# DAUGHTERBOARD.net
KiCad netlist of a schematic drawn in Altium Designer
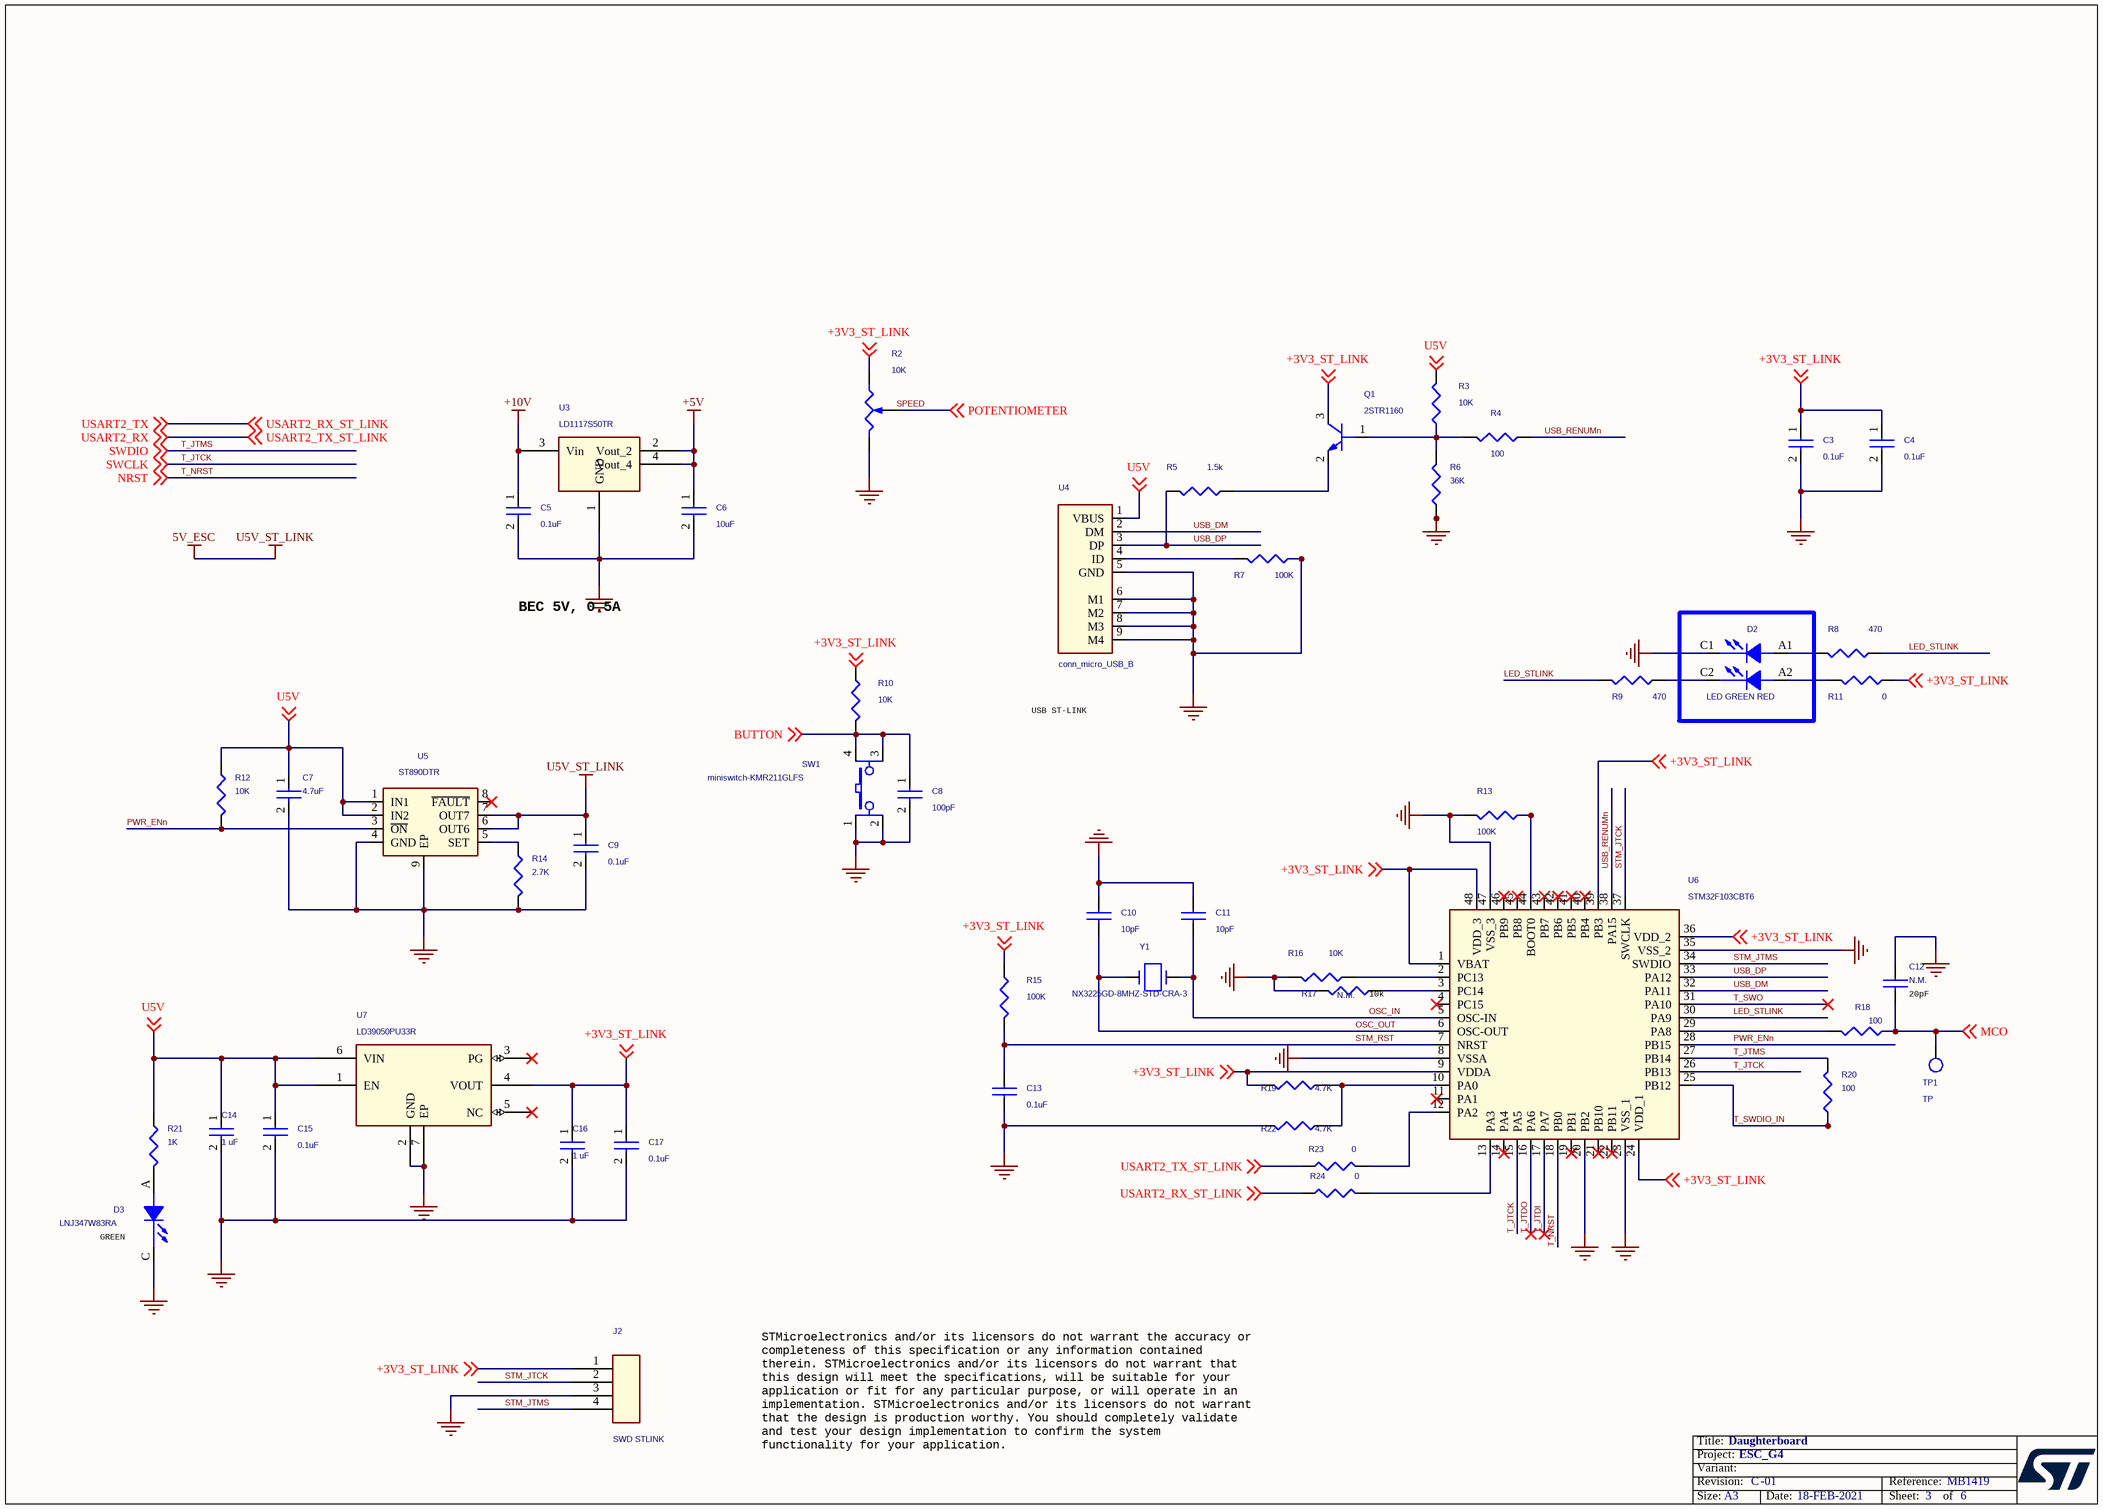
[diagram p0: DAUGHTERBOARD.SchDoc]

(export (version "E")
  (design (tool "Eeschema 10.0.6"))
  (components
    (comp (ref "C3")
      (value "0.1uF")
      (footprint "C_0402")
      (description "CAP CER 0.1UF 16V X7R 0402")
      (fields (field (name "MANUFACTURER") "Wurth Electronics Inc.") (field (name "TOLERANCE") "10%"))
      (libsource (lib "*") (part "CAP_Dup1"))
    )
    (comp (ref "C4")
      (value "0.1uF")
      (footprint "C_0402")
      (description "CAP CER 0.1UF 16V X7R 0402")
      (fields (field (name "MANUFACTURER") "Wurth Electronics Inc.") (field (name "TOLERANCE") "10%"))
      (libsource (lib "*") (part "CAP_Dup1"))
    )
    (comp (ref "C5")
      (value "0.1uF")
      (footprint "C_0402")
      (description "CAP CER 0.1UF 16V X7R 0402")
      (fields (field (name "MANUFACTURER") "Wurth Electronics Inc.") (field (name "TOLERANCE") "10%"))
      (libsource (lib "*") (part "CAP_Dup1"))
    )
    (comp (ref "C6")
      (value "10uF")
      (footprint "C_0805")
      (description "CAP CER 10UF 16V X5R 0805")
      (fields (field (name "MANUFACTURER") "Wurth Electronics Inc.") (field (name "TOLERANCE") "20%"))
      (libsource (lib "*") (part "CAP_Dup1"))
    )
    (comp (ref "C7")
      (value "4.7uF")
      (footprint "C_0805")
      (description "CAP CER 4.7UF 16V X5R 0805")
      (fields (field (name "PART_NUMBER") "TMP-410") (field (name "TOLERANCE") "20%"))
      (libsource (lib "*") (part "CAP_Dup1"))
    )
    (comp (ref "C8")
      (value "100pF")
      (footprint "C_0402")
      (description "CAP CER 100PF 10V C0G/NP0 0402")
      (fields (field (name "PART_NUMBER") "TMP-412") (field (name "TOLERANCE") "5%"))
      (libsource (lib "*") (part "CAP_Dup1"))
    )
    (comp (ref "C9")
      (value "0.1uF")
      (footprint "C_0402")
      (description "CAP CER 0.1UF 16V X7R 0402")
      (fields (field (name "MANUFACTURER") "Wurth Electronics Inc.") (field (name "TOLERANCE") "10%"))
      (libsource (lib "*") (part "CAP_Dup1"))
    )
    (comp (ref "C10")
      (value "10pF")
      (footprint "C_0402")
      (description "CAP CER 10PF 10V C0G/NP0 0402")
      (fields (field (name "PART_NUMBER") "TMP-395") (field (name "TOLERANCE") "5%"))
      (libsource (lib "*") (part "CAP_7"))
    )
    (comp (ref "C11")
      (value "10pF")
      (footprint "C_0402")
      (description "CAP CER 10PF 10V C0G/NP0 0402")
      (fields (field (name "PART_NUMBER") "TMP-395") (field (name "TOLERANCE") "5%"))
      (libsource (lib "*") (part "CAP_7"))
    )
    (comp (ref "C12")
      (value "N.M.")
      (footprint "C_0402")
      (description "CAP CER 0402-NOT MOUNTED")
      (fields (field (name "PART_NUMBER") "TMP-408"))
      (libsource (lib "*") (part "CAP_6"))
    )
    (comp (ref "C13")
      (value "0.1uF")
      (footprint "C_0402")
      (description "CAP CER 0.1UF 16V X7R 0402")
      (fields (field (name "PART_NUMBER") "CAP-00000053") (field (name "TOLERANCE") "10%"))
      (libsource (lib "*") (part "CAP_8"))
    )
    (comp (ref "C14")
      (value "1 uF")
      (footprint "C_0603")
      (description "CAP CER 1UF 16V X5R 0603")
      (fields (field (name "PART_NUMBER") "TMP-302") (field (name "TOLERANCE") "10%"))
      (libsource (lib "*") (part "CAP_Dup1"))
    )
    (comp (ref "C15")
      (value "0.1uF")
      (footprint "C_0603")
      (description "CAP CER 0.1UF 16V X7R 0603")
      (fields (field (name "MANUFACTURER") "Wurth Electronics Inc.") (field (name "TOLERANCE") "10%"))
      (libsource (lib "*") (part "CAP_Dup1"))
    )
    (comp (ref "C16")
      (value "1 uF")
      (footprint "C_0603")
      (description "CAP CER 1UF 16V X5R 0603")
      (fields (field (name "PART_NUMBER") "TMP-302") (field (name "TOLERANCE") "10%"))
      (libsource (lib "*") (part "CAP_Dup1"))
    )
    (comp (ref "C17")
      (value "0.1uF")
      (footprint "C_0402")
      (description "CAP CER 0.1UF 16V X7R 0402")
      (fields (field (name "PART_NUMBER") "CAP-00000053") (field (name "TOLERANCE") "10%"))
      (libsource (lib "*") (part "CAP_Dup1"))
    )
    (comp (ref "D2")
      (value "LED GREEN RED")
      (footprint "Led_bicolor_3528-PLCC-4")
      (description "LED GREEN/RED CLEAR 4PLCC SMD")
      (fields (field (name "PART_NUMBER") "TMP-705") (field (name "MANUFACTURER") "Wurth Electronics Inc."))
      (libsource (lib "*") (part "LED_BICOLOR"))
    )
    (comp (ref "D3")
      (value "LNJ347W83RA")
      (footprint "D_0402_Led_green")
      (description "LED GREEN 0402 SMD")
      (fields (field (name "MANUFACTURER") "Everlight Electronics") (field (name "PART_NUMBER") "TMP-187"))
      (libsource (lib "*") (part "LED"))
    )
    (comp (ref "J2")
      (value "SWD STLINK")
      (footprint "strip4_100m_v")
      (description "SOLDER PADS")
      (libsource (lib "*") (part "CON4"))
    )
    (comp (ref "Q1")
      (value "2STR1160")
      (footprint "sot23-3p97_255x140l40x40n")
      (description "TRANS NPN 60V 1A SOT-23")
      (fields (field (name "PART_NUMBER") "TMP-433") (field (name "MANUFACTURER") "STMicroelectronics"))
      (libsource (lib "*") (part "BJT_NPN_BEC"))
    )
    (comp (ref "R2")
      (value "10K")
      (footprint "trimmer-3386P_T")
      (description "TRIMMER 10K OHM 0.5W PC PIN")
      (fields (field (name "PART_NUMBER") "TMP-491") (field (name "TOLERANCE") "10%"))
      (libsource (lib "*") (part "POT"))
    )
    (comp (ref "R3")
      (value "10K")
      (footprint "R_0402")
      (description "RES SMD 10K OHM 1% 1/16W 0402")
      (fields (field (name "MANUFACTURER") "Yageo") (field (name "TOLERANCE") "1%"))
      (libsource (lib "*") (part "RES"))
    )
    (comp (ref "R4")
      (value "100")
      (footprint "R_0402")
      (description "RES SMD 100 OHM 1% 1/16W 0402")
      (fields (field (name "PART_NUMBER") "TMP-406") (field (name "TOLERANCE") "1%"))
      (libsource (lib "*") (part "RES"))
    )
    (comp (ref "R5")
      (value "1.5k")
      (footprint "R_0402")
      (description "RES SMD 1.5K OHM 1% 1/16W 0402")
      (fields (field (name "PART_NUMBER") "TMP-393") (field (name "TOLERANCE") "1%"))
      (libsource (lib "*") (part "RES"))
    )
    (comp (ref "R6")
      (value "36K")
      (footprint "R_0402")
      (description "RES SMD 36K OHM 1% 1/16W 0402")
      (fields (field (name "MANUFACTURER") "Yageo") (field (name "TOLERANCE") "1%"))
      (libsource (lib "*") (part "RES"))
    )
    (comp (ref "R7")
      (value "100K")
      (footprint "R_0402")
      (description "RES SMD 100K OHM 1% 1/16W 0402")
      (fields (field (name "MANUFACTURER") "TE Connectivity Passive Product") (field (name "TOLERANCE") "1%"))
      (libsource (lib "*") (part "RES"))
    )
    (comp (ref "R8")
      (value "470")
      (footprint "R_0402")
      (description "RES SMD 100 OHM 1% 1/16W 0402")
      (fields (field (name "PART_NUMBER") "TMP-406") (field (name "TOLERANCE") "1%"))
      (libsource (lib "*") (part "RES"))
    )
    (comp (ref "R9")
      (value "470")
      (footprint "R_0402")
      (description "RES SMD 100 OHM 1% 1/16W 0402")
      (fields (field (name "MANUFACTURER") "TE Connectivity Passive Product") (field (name "TOLERANCE") "1%"))
      (libsource (lib "*") (part "RES"))
    )
    (comp (ref "R10")
      (value "10K")
      (footprint "R_0402")
      (description "RES SMD 10K OHM 1% 1/16W 0402")
      (fields (field (name "PART_NUMBER") "TMP-396") (field (name "TOLERANCE") "1%"))
      (libsource (lib "*") (part "RES"))
    )
    (comp (ref "R11")
      (value "0")
      (footprint "R_0402")
      (description "RES SMD 0 OHM JUMPER 1/16W 0402")
      (fields (field (name "MANUFACTURER") "Vishay Dale") (field (name "TOLERANCE") "Jumper"))
      (libsource (lib "*") (part "RES"))
    )
    (comp (ref "R12")
      (value "10K")
      (footprint "R_0402")
      (description "RES SMD 10K OHM 1% 1/16W 0402")
      (fields (field (name "MANUFACTURER") "Yageo") (field (name "TOLERANCE") "1%"))
      (libsource (lib "*") (part "RES"))
    )
    (comp (ref "R13")
      (value "100K")
      (footprint "R_0402")
      (description "RES SMD 100K OHM 1% 1/16W 0402")
      (fields (field (name "MANUFACTURER") "TE Connectivity Passive Product") (field (name "TOLERANCE") "1%"))
      (libsource (lib "*") (part "RES"))
    )
    (comp (ref "R14")
      (value "2.7K")
      (footprint "R_0402")
      (description "RES SMD 2.7K OHM 1% 1/16W 0402")
      (fields (field (name "PART_NUMBER") "TMP-411") (field (name "TOLERANCE") "1%"))
      (libsource (lib "*") (part "RES"))
    )
    (comp (ref "R15")
      (value "100K")
      (footprint "R_0402")
      (description "RES SMD 100K OHM 1% 1/16W 0402")
      (fields (field (name "PART_NUMBER") "TMP-405") (field (name "TOLERANCE") "1%"))
      (libsource (lib "*") (part "RES"))
    )
    (comp (ref "R16")
      (value "10K")
      (footprint "R_0402")
      (description "RES SMD 10K OHM 1% 1/16W 0402")
      (fields (field (name "PART_NUMBER") "TMP-396") (field (name "TOLERANCE") "1%"))
      (libsource (lib "*") (part "RES"))
    )
    (comp (ref "R17")
      (value "N.M.")
      (footprint "R_0402")
      (description "RES SMD 0402 - NOT MOUNTED")
      (fields (field (name "PART_NUMBER") "TMP-404"))
      (libsource (lib "*") (part "RES"))
    )
    (comp (ref "R18")
      (value "100")
      (footprint "R_0402")
      (description "RES SMD 100 OHM 1% 1/16W 0402")
      (fields (field (name "MANUFACTURER") "TE Connectivity Passive Product") (field (name "TOLERANCE") "1%"))
      (libsource (lib "*") (part "RES"))
    )
    (comp (ref "R19")
      (value "4.7K")
      (footprint "R_0402")
      (description "RES SMD 4.7K OHM 1% 1/16W 0402")
      (fields (field (name "PART_NUMBER") "TMP-403") (field (name "TOLERANCE") "1%"))
      (libsource (lib "*") (part "RES"))
    )
    (comp (ref "R20")
      (value "100")
      (footprint "R_0402")
      (description "RES SMD 100 OHM 1% 1/16W 0402")
      (fields (field (name "PART_NUMBER") "TMP-406") (field (name "TOLERANCE") "1%"))
      (libsource (lib "*") (part "RES"))
    )
    (comp (ref "R21")
      (value "1K")
      (footprint "R_0402")
      (description "RES SMD 1K OHM 1% 1/16W 0402")
      (fields (field (name "PART_NUMBER") "TMP-352") (field (name "TOLERANCE") "1%"))
      (libsource (lib "*") (part "RES"))
    )
    (comp (ref "R22")
      (value "4.7K")
      (footprint "R_0402")
      (description "RES SMD 4.7K OHM 1% 1/16W 0402")
      (fields (field (name "PART_NUMBER") "TMP-403") (field (name "TOLERANCE") "1%"))
      (libsource (lib "*") (part "RES"))
    )
    (comp (ref "R23")
      (value "0")
      (footprint "JUMPER_0603_DROP")
      (description "RES SMD 0 OHM JUMPER 1/10W 0603")
      (fields
        (field (name "MANUFACTURER") "Panasonic Electronic Components")
        (field (name "TOLERANCE") "Jumper")
      )
      (libsource (lib "*") (part "RES"))
    )
    (comp (ref "R24")
      (value "0")
      (footprint "JUMPER_0603_DROP")
      (description "RES SMD 0 OHM JUMPER 1/10W 0603")
      (fields (field (name "PART_NUMBER") "RES-00000056") (field (name "TOLERANCE") "Jumper"))
      (libsource (lib "*") (part "RES"))
    )
    (comp (ref "SW1")
      (value "miniswitch-KMR211GLFS")
      (footprint "switch_SMT_4_2x2_8mm")
      (description "SWITCH TACTILE SPST-NO 0.05A 32V")
      (fields (field (name "MANUFACTURER") "C&K") (field (name "PART_NUMBER") "TMP-285"))
      (libsource (lib "*") (part "PUSHBUTTON-SPST-2"))
    )
    (comp (ref "TP1")
      (value "TP")
      (footprint "test_point_100_smd")
      (description "TEST POINT 1MM  SMD PADSTASCK")
      (fields (field (name "PART_NUMBER") "TMP-386"))
      (libsource (lib "*") (part "TESTPOINT"))
    )
    (comp (ref "U3")
      (value "LD1117S50TR")
      (footprint "sot223-4p230_700x190l65x72")
      (description "IC REG LINEAR 5V 800MA SOT223")
      (fields (field (name "MANUFACTURER") "STMicroelectronics") (field (name "PART_NUMBER") "TMP-381"))
      (libsource (lib "*") (part "LD1117SxxxTR_0"))
    )
    (comp (ref "U4")
      (value "conn_micro_USB_B")
      (footprint "conn_micro_USB_B_SMD")
      (description "CONN RCPT 5POS MICRO USB R/A")
      (fields (field (name "MANUFACTURER") "Molex, LLC") (field (name "PART_NUMBER") "TMP-434"))
      (libsource (lib "*") (part "USB_MICRO"))
    )
    (comp (ref "U5")
      (value "ST890DTR")
      (footprint "son9p65_300x300x90l30x30t240-1")
      (description "IC PWR SWITCH 1.2A HISIDE 8-DFN")
      (fields (field (name "MANUFACTURER") "STMicroelectronics") (field (name "PART_NUMBER") "TMP-432"))
      (libsource (lib "*") (part "ST890DTR"))
    )
    (comp (ref "U6")
      (value "STM32F103CBT6")
      (footprint "qfp48p50_900x900x160l60x22n")
      (description "IC MCU 32BIT 128KB FLASH 48LQFP")
      (fields (field (name "PART_NUMBER") "TMP-399") (field (name "MANUFACTURER") "STMicroelectronics"))
      (libsource (lib "*") (part "STM32F103CBT6"))
    )
    (comp (ref "U7")
      (value "LD39050PU33R")
      (footprint "son7p95_300x300x100l40x34t23-1")
      (description "IC REG LINEAR 3.3V 500MA 6DFN")
      (fields (field (name "PART_NUMBER") "TMP-358") (field (name "MANUFACTURER") "STMicroelectronics"))
      (libsource (lib "*") (part "LD39050PU33R"))
    )
    (comp (ref "Y1")
      (value "NX3225GD-8MHZ-STD-CRA-3")
      (footprint "xtaldfn2_320x250x100l130x230")
      (description "CRYSTAL 8.0000MHZ 8PF SMD")
      (fields (field (name "MANUFACTURER") "NDK America, Inc.") (field (name "PART_NUMBER") "TMP-435"))
      (libsource (lib "*") (part "crystal"))
    )
  )
  (nets
    (net (code "1") (name "+3V3_ST_LINK") (class "Default")
      (node (ref "C16") (pin "1") (pinfunction "1_1") (pintype "passive"))
      (node (ref "C17") (pin "1") (pinfunction "1_1") (pintype "passive"))
      (node (ref "C3") (pin "1") (pinfunction "1_1") (pintype "passive"))
      (node (ref "C4") (pin "1") (pinfunction "1_1") (pintype "passive"))
      (node (ref "J2") (pin "1") (pinfunction "1_1") (pintype "passive"))
      (node (ref "Q1") (pin "3") (pinfunction "C_3") (pintype "passive"))
      (node (ref "R10") (pin "1") (pinfunction "1_1") (pintype "passive"))
      (node (ref "R11") (pin "1") (pinfunction "1_1") (pintype "passive"))
      (node (ref "R15") (pin "1") (pinfunction "1_1") (pintype "passive"))
      (node (ref "R19") (pin "2") (pinfunction "2_2") (pintype "passive"))
      (node (ref "R2") (pin "3") (pinfunction "B_3") (pintype "passive"))
      (node (ref "U6") (pin "1") (pinfunction "VBAT_1") (pintype "passive"))
      (node (ref "U6") (pin "24") (pinfunction "VDD_1_24") (pintype "passive"))
      (node (ref "U6") (pin "36") (pinfunction "VDD_2_36") (pintype "passive"))
      (node (ref "U6") (pin "39") (pinfunction "PB3_39") (pintype "passive"))
      (node (ref "U6") (pin "48") (pinfunction "VDD_3_48") (pintype "passive"))
      (node (ref "U6") (pin "9") (pinfunction "VDDA_9") (pintype "passive"))
      (node (ref "U7") (pin "4") (pinfunction "VOUT_4") (pintype "power_in"))
    )
    (net (code "2") (name "+5V") (class "Default")
      (node (ref "C6") (pin "1") (pinfunction "1_1") (pintype "passive"))
      (node (ref "U3") (pin "2") (pinfunction "Vout_2_2") (pintype "passive"))
      (node (ref "U3") (pin "4") (pinfunction "Vout_4_4") (pintype "passive"))
    )
    (net (code "3") (name "+10V") (class "Default")
      (node (ref "C5") (pin "1") (pinfunction "1_1") (pintype "passive"))
      (node (ref "U3") (pin "3") (pinfunction "Vin_3") (pintype "passive"))
    )
    (net (code "4") (name "/LED_STLINK") (class "Default")
      (node (ref "R8") (pin "1") (pinfunction "1_1") (pintype "passive"))
      (node (ref "R9") (pin "2") (pinfunction "2_2") (pintype "passive"))
      (node (ref "U6") (pin "30") (pinfunction "PA9_30") (pintype "passive"))
    )
    (net (code "5") (name "/OSC_IN") (class "Default")
      (node (ref "C11") (pin "2") (pinfunction "2_2") (pintype "passive"))
      (node (ref "U6") (pin "5") (pinfunction "OSC-IN_5") (pintype "passive"))
      (node (ref "Y1") (pin "1") (pinfunction "1_1") (pintype "passive"))
    )
    (net (code "6") (name "/OSC_OUT") (class "Default")
      (node (ref "C10") (pin "2") (pinfunction "2_2") (pintype "passive"))
      (node (ref "U6") (pin "6") (pinfunction "OSC-OUT_6") (pintype "passive"))
      (node (ref "Y1") (pin "2") (pinfunction "2_2") (pintype "passive"))
    )
    (net (code "7") (name "/PWR_ENn") (class "Default")
      (node (ref "R12") (pin "2") (pinfunction "2_2") (pintype "passive"))
      (node (ref "U5") (pin "3") (pinfunction "~{ON}_3") (pintype "passive"))
      (node (ref "U6") (pin "28") (pinfunction "PB15_28") (pintype "passive"))
    )
    (net (code "8") (name "/STM_JTCK") (class "Default")
      (node (ref "J2") (pin "2") (pinfunction "2_2") (pintype "passive"))
      (node (ref "U6") (pin "37") (pinfunction "SWCLK_37") (pintype "passive"))
    )
    (net (code "9") (name "/STM_JTMS") (class "Default")
      (node (ref "J2") (pin "4") (pinfunction "4_4") (pintype "passive"))
      (node (ref "U6") (pin "34") (pinfunction "SWDIO_34") (pintype "passive"))
    )
    (net (code "10") (name "/STM_RST") (class "Default")
      (node (ref "C13") (pin "1") (pinfunction "1_1") (pintype "passive"))
      (node (ref "R15") (pin "2") (pinfunction "2_2") (pintype "passive"))
      (node (ref "U6") (pin "7") (pinfunction "NRST_7") (pintype "passive"))
    )
    (net (code "11") (name "/T_JTDI") (class "Default")
      (node (ref "U6") (pin "17") (pinfunction "PA7_17") (pintype "passive+no_connect"))
    )
    (net (code "12") (name "/T_JTDO") (class "Default")
      (node (ref "U6") (pin "16") (pinfunction "PA6_16") (pintype "passive+no_connect"))
    )
    (net (code "13") (name "/T_SWDIO_IN") (class "Default")
      (node (ref "R20") (pin "1") (pinfunction "1_1") (pintype "passive"))
      (node (ref "U6") (pin "25") (pinfunction "PB12_25") (pintype "passive"))
    )
    (net (code "14") (name "/T_SWO") (class "Default")
      (node (ref "U6") (pin "31") (pinfunction "PA10_31") (pintype "passive+no_connect"))
    )
    (net (code "15") (name "/USB_DM") (class "Default")
      (node (ref "U4") (pin "2") (pinfunction "DM_2") (pintype "passive"))
      (node (ref "U6") (pin "32") (pinfunction "PA11_32") (pintype "passive"))
    )
    (net (code "16") (name "/USB_DP") (class "Default")
      (node (ref "R5") (pin "2") (pinfunction "2_2") (pintype "passive"))
      (node (ref "U4") (pin "3") (pinfunction "DP_3") (pintype "passive"))
      (node (ref "U6") (pin "33") (pinfunction "PA12_33") (pintype "passive"))
    )
    (net (code "17") (name "/USB_RENUMn") (class "Default")
      (node (ref "R4") (pin "1") (pinfunction "1_1") (pintype "passive"))
      (node (ref "U6") (pin "38") (pinfunction "PA15_38") (pintype "passive"))
    )
    (net (code "18") (name "5V_ESC") (class "Default")
      (node (ref "C9") (pin "1") (pinfunction "1_1") (pintype "passive"))
      (node (ref "U5") (pin "6") (pinfunction "OUT6_6") (pintype "passive"))
      (node (ref "U5") (pin "7") (pinfunction "OUT7_7") (pintype "passive"))
    )
    (net (code "19") (name "BUTTON") (class "Default")
      (node (ref "C8") (pin "1") (pinfunction "1_1") (pintype "passive"))
      (node (ref "R10") (pin "2") (pinfunction "2_2") (pintype "passive"))
      (node (ref "SW1") (pin "3") (pinfunction "3_3") (pintype "passive"))
      (node (ref "SW1") (pin "4") (pinfunction "4_4") (pintype "passive"))
    )
    (net (code "20") (name "GND") (class "Default")
      (node (ref "C10") (pin "1") (pinfunction "1_1") (pintype "passive"))
      (node (ref "C11") (pin "1") (pinfunction "1_1") (pintype "passive"))
      (node (ref "C12") (pin "1") (pinfunction "1_1") (pintype "passive"))
      (node (ref "C13") (pin "2") (pinfunction "2_2") (pintype "passive"))
      (node (ref "C14") (pin "2") (pinfunction "2_2") (pintype "passive"))
      (node (ref "C15") (pin "2") (pinfunction "2_2") (pintype "passive"))
      (node (ref "C16") (pin "2") (pinfunction "2_2") (pintype "passive"))
      (node (ref "C17") (pin "2") (pinfunction "2_2") (pintype "passive"))
      (node (ref "C3") (pin "2") (pinfunction "2_2") (pintype "passive"))
      (node (ref "C4") (pin "2") (pinfunction "2_2") (pintype "passive"))
      (node (ref "C5") (pin "2") (pinfunction "2_2") (pintype "passive"))
      (node (ref "C6") (pin "2") (pinfunction "2_2") (pintype "passive"))
      (node (ref "C7") (pin "2") (pinfunction "2_2") (pintype "passive"))
      (node (ref "C8") (pin "2") (pinfunction "2_2") (pintype "passive"))
      (node (ref "C9") (pin "2") (pinfunction "2_2") (pintype "passive"))
      (node (ref "D2") (pin "C1") (pinfunction "CATHODE1_C1") (pintype "passive"))
      (node (ref "D3") (pin "C") (pinfunction "CATHODE_C") (pintype "passive"))
      (node (ref "J2") (pin "3") (pinfunction "3_3") (pintype "passive"))
      (node (ref "R13") (pin "2") (pinfunction "2_2") (pintype "passive"))
      (node (ref "R14") (pin "2") (pinfunction "2_2") (pintype "passive"))
      (node (ref "R16") (pin "2") (pinfunction "2_2") (pintype "passive"))
      (node (ref "R17") (pin "2") (pinfunction "2_2") (pintype "passive"))
      (node (ref "R2") (pin "1") (pinfunction "A_1") (pintype "passive"))
      (node (ref "R22") (pin "2") (pinfunction "2_2") (pintype "passive"))
      (node (ref "R6") (pin "1") (pinfunction "1_1") (pintype "passive"))
      (node (ref "R7") (pin "1") (pinfunction "1_1") (pintype "passive"))
      (node (ref "SW1") (pin "1") (pinfunction "1_1") (pintype "passive"))
      (node (ref "SW1") (pin "2") (pinfunction "2_2") (pintype "passive"))
      (node (ref "U3") (pin "1") (pinfunction "GND_1") (pintype "power_in"))
      (node (ref "U4") (pin "5") (pinfunction "GND_5") (pintype "passive"))
      (node (ref "U4") (pin "6") (pinfunction "M1_6") (pintype "passive"))
      (node (ref "U4") (pin "7") (pinfunction "M2_7") (pintype "passive"))
      (node (ref "U4") (pin "8") (pinfunction "M3_8") (pintype "passive"))
      (node (ref "U4") (pin "9") (pinfunction "M4_9") (pintype "passive"))
      (node (ref "U5") (pin "4") (pinfunction "GND_4") (pintype "passive"))
      (node (ref "U5") (pin "9") (pinfunction "EP_9") (pintype "passive"))
      (node (ref "U6") (pin "20") (pinfunction "PB2_20") (pintype "passive"))
      (node (ref "U6") (pin "23") (pinfunction "VSS_1_23") (pintype "passive"))
      (node (ref "U6") (pin "35") (pinfunction "VSS_2_35") (pintype "passive"))
      (node (ref "U6") (pin "47") (pinfunction "VSS_3_47") (pintype "passive"))
      (node (ref "U6") (pin "8") (pinfunction "VSSA_8") (pintype "passive"))
      (node (ref "U7") (pin "2") (pinfunction "GND_2") (pintype "power_in"))
      (node (ref "U7") (pin "7") (pinfunction "EP_7") (pintype "power_in"))
    )
    (net (code "21") (name "MCO") (class "Default")
      (node (ref "C12") (pin "2") (pinfunction "2_2") (pintype "passive"))
      (node (ref "R18") (pin "1") (pinfunction "1_1") (pintype "passive"))
      (node (ref "TP1") (pin "1") (pinfunction "1_1") (pintype "passive"))
    )
    (net (code "22") (name "NRST") (class "Default")
      (node (ref "U6") (pin "18") (pinfunction "PB0_18") (pintype "passive"))
    )
    (net (code "23") (name "Net-(D2-ANODE1)") (class "Default")
      (node (ref "D2") (pin "A1") (pinfunction "ANODE1_A1") (pintype "passive"))
      (node (ref "R8") (pin "2") (pinfunction "2_2") (pintype "passive"))
    )
    (net (code "24") (name "Net-(D2-ANODE2)") (class "Default")
      (node (ref "D2") (pin "A2") (pinfunction "ANODE2_A2") (pintype "passive"))
      (node (ref "R11") (pin "2") (pinfunction "2_2") (pintype "passive"))
    )
    (net (code "25") (name "Net-(D2-CATHODE2)") (class "Default")
      (node (ref "D2") (pin "C2") (pinfunction "CATHODE2_C2") (pintype "passive"))
      (node (ref "R9") (pin "1") (pinfunction "1_1") (pintype "passive"))
    )
    (net (code "26") (name "Net-(D3-ANODE)") (class "Default")
      (node (ref "D3") (pin "A") (pinfunction "ANODE_A") (pintype "passive"))
      (node (ref "R21") (pin "2") (pinfunction "2_2") (pintype "passive"))
    )
    (net (code "27") (name "Net-(Q1-B)") (class "Default")
      (node (ref "Q1") (pin "1") (pinfunction "B_1") (pintype "passive"))
      (node (ref "R3") (pin "1") (pinfunction "1_1") (pintype "passive"))
      (node (ref "R4") (pin "2") (pinfunction "2_2") (pintype "passive"))
      (node (ref "R6") (pin "2") (pinfunction "2_2") (pintype "passive"))
    )
    (net (code "28") (name "Net-(Q1-E)") (class "Default")
      (node (ref "Q1") (pin "2") (pinfunction "E_2") (pintype "passive"))
      (node (ref "R5") (pin "1") (pinfunction "1_1") (pintype "passive"))
    )
    (net (code "29") (name "Net-(U4-ID)") (class "Default")
      (node (ref "R7") (pin "2") (pinfunction "2_2") (pintype "passive"))
      (node (ref "U4") (pin "4") (pinfunction "ID_4") (pintype "passive"))
    )
    (net (code "30") (name "Net-(U5-SET)") (class "Default")
      (node (ref "R14") (pin "1") (pinfunction "1_1") (pintype "passive"))
      (node (ref "U5") (pin "5") (pinfunction "SET_5") (pintype "passive"))
    )
    (net (code "31") (name "Net-(U6-BOOT0)") (class "Default")
      (node (ref "R13") (pin "1") (pinfunction "1_1") (pintype "passive"))
      (node (ref "U6") (pin "44") (pinfunction "BOOT0_44") (pintype "passive"))
    )
    (net (code "32") (name "Net-(U6-PA0)") (class "Default")
      (node (ref "R19") (pin "1") (pinfunction "1_1") (pintype "passive"))
      (node (ref "R22") (pin "1") (pinfunction "1_1") (pintype "passive"))
      (node (ref "U6") (pin "10") (pinfunction "PA0_10") (pintype "passive"))
    )
    (net (code "33") (name "Net-(U6-PA2)") (class "Default")
      (node (ref "R23") (pin "2") (pinfunction "2_2") (pintype "passive"))
      (node (ref "U6") (pin "12") (pinfunction "PA2_12") (pintype "passive"))
    )
    (net (code "34") (name "Net-(U6-PA3)") (class "Default")
      (node (ref "R24") (pin "2") (pinfunction "2_2") (pintype "passive"))
      (node (ref "U6") (pin "13") (pinfunction "PA3_13") (pintype "passive"))
    )
    (net (code "35") (name "Net-(U6-PA8)") (class "Default")
      (node (ref "R18") (pin "2") (pinfunction "2_2") (pintype "passive"))
      (node (ref "U6") (pin "29") (pinfunction "PA8_29") (pintype "passive"))
    )
    (net (code "36") (name "Net-(U6-PC13)") (class "Default")
      (node (ref "R16") (pin "1") (pinfunction "1_1") (pintype "passive"))
      (node (ref "U6") (pin "2") (pinfunction "PC13_2") (pintype "passive"))
    )
    (net (code "37") (name "Net-(U6-PC14)") (class "Default")
      (node (ref "R17") (pin "1") (pinfunction "1_1") (pintype "passive"))
      (node (ref "U6") (pin "3") (pinfunction "PC14_3") (pintype "passive"))
    )
    (net (code "38") (name "POTENTIOMETER") (class "Default")
      (node (ref "R2") (pin "2") (pinfunction "WIPER_2") (pintype "passive"))
    )
    (net (code "39") (name "SWCLK") (class "Default")
      (node (ref "U6") (pin "15") (pinfunction "PA5_15") (pintype "passive"))
      (node (ref "U6") (pin "26") (pinfunction "PB13_26") (pintype "passive"))
    )
    (net (code "40") (name "SWDIO") (class "Default")
      (node (ref "R20") (pin "2") (pinfunction "2_2") (pintype "passive"))
      (node (ref "U6") (pin "27") (pinfunction "PB14_27") (pintype "passive"))
    )
    (net (code "41") (name "U5V") (class "Default")
      (node (ref "C14") (pin "1") (pinfunction "1_1") (pintype "passive"))
      (node (ref "C15") (pin "1") (pinfunction "1_1") (pintype "passive"))
      (node (ref "C7") (pin "1") (pinfunction "1_1") (pintype "passive"))
      (node (ref "R12") (pin "1") (pinfunction "1_1") (pintype "passive"))
      (node (ref "R21") (pin "1") (pinfunction "1_1") (pintype "passive"))
      (node (ref "R3") (pin "2") (pinfunction "2_2") (pintype "passive"))
      (node (ref "U4") (pin "1") (pinfunction "VBUS_1") (pintype "passive"))
      (node (ref "U5") (pin "1") (pinfunction "IN1_1") (pintype "passive"))
      (node (ref "U5") (pin "2") (pinfunction "IN2_2") (pintype "passive"))
      (node (ref "U7") (pin "1") (pinfunction "EN_1") (pintype "power_in"))
      (node (ref "U7") (pin "6") (pinfunction "VIN_6") (pintype "power_in"))
    )
    (net (code "42") (name "USART2_RX") (class "Default")
      (node (ref "R23") (pin "1") (pinfunction "1_1") (pintype "passive"))
    )
    (net (code "43") (name "USART2_RX_ST_LINK") (class "Default")
      (node (ref "R24") (pin "1") (pinfunction "1_1") (pintype "passive"))
    )
    (net (code "44") (name "unconnected-(U5-~{FAULT}-Pad8)") (class "Default")
      (node (ref "U5") (pin "8") (pinfunction "~{FAULT}_8") (pintype "passive+no_connect"))
    )
    (net (code "45") (name "unconnected-(U6-PA1-Pad11)") (class "Default")
      (node (ref "U6") (pin "11") (pinfunction "PA1_11") (pintype "passive+no_connect"))
    )
    (net (code "46") (name "unconnected-(U6-PA4-Pad14)") (class "Default")
      (node (ref "U6") (pin "14") (pinfunction "PA4_14") (pintype "passive+no_connect"))
    )
    (net (code "47") (name "unconnected-(U6-PB1-Pad19)") (class "Default")
      (node (ref "U6") (pin "19") (pinfunction "PB1_19") (pintype "passive+no_connect"))
    )
    (net (code "48") (name "unconnected-(U6-PB4-Pad40)") (class "Default")
      (node (ref "U6") (pin "40") (pinfunction "PB4_40") (pintype "passive+no_connect"))
    )
    (net (code "49") (name "unconnected-(U6-PB5-Pad41)") (class "Default")
      (node (ref "U6") (pin "41") (pinfunction "PB5_41") (pintype "passive+no_connect"))
    )
    (net (code "50") (name "unconnected-(U6-PB6-Pad42)") (class "Default")
      (node (ref "U6") (pin "42") (pinfunction "PB6_42") (pintype "passive+no_connect"))
    )
    (net (code "51") (name "unconnected-(U6-PB7-Pad43)") (class "Default")
      (node (ref "U6") (pin "43") (pinfunction "PB7_43") (pintype "passive+no_connect"))
    )
    (net (code "52") (name "unconnected-(U6-PB8-Pad45)") (class "Default")
      (node (ref "U6") (pin "45") (pinfunction "PB8_45") (pintype "passive+no_connect"))
    )
    (net (code "53") (name "unconnected-(U6-PB9-Pad46)") (class "Default")
      (node (ref "U6") (pin "46") (pinfunction "PB9_46") (pintype "passive+no_connect"))
    )
    (net (code "54") (name "unconnected-(U6-PB10-Pad21)") (class "Default")
      (node (ref "U6") (pin "21") (pinfunction "PB10_21") (pintype "passive+no_connect"))
    )
    (net (code "55") (name "unconnected-(U6-PB11-Pad22)") (class "Default")
      (node (ref "U6") (pin "22") (pinfunction "PB11_22") (pintype "passive+no_connect"))
    )
    (net (code "56") (name "unconnected-(U6-PC15-Pad4)") (class "Default")
      (node (ref "U6") (pin "4") (pinfunction "PC15_4") (pintype "passive+no_connect"))
    )
    (net (code "57") (name "unconnected-(U7-NC-Pad5)") (class "Default")
      (node (ref "U7") (pin "5") (pinfunction "NC_5") (pintype "bidirectional+no_connect"))
    )
    (net (code "58") (name "unconnected-(U7-PG-Pad3)") (class "Default")
      (node (ref "U7") (pin "3") (pinfunction "PG_3") (pintype "bidirectional+no_connect"))
    )
  )
)
